# Digital__IO.net
KiCad netlist of a schematic drawn in Altium Designer
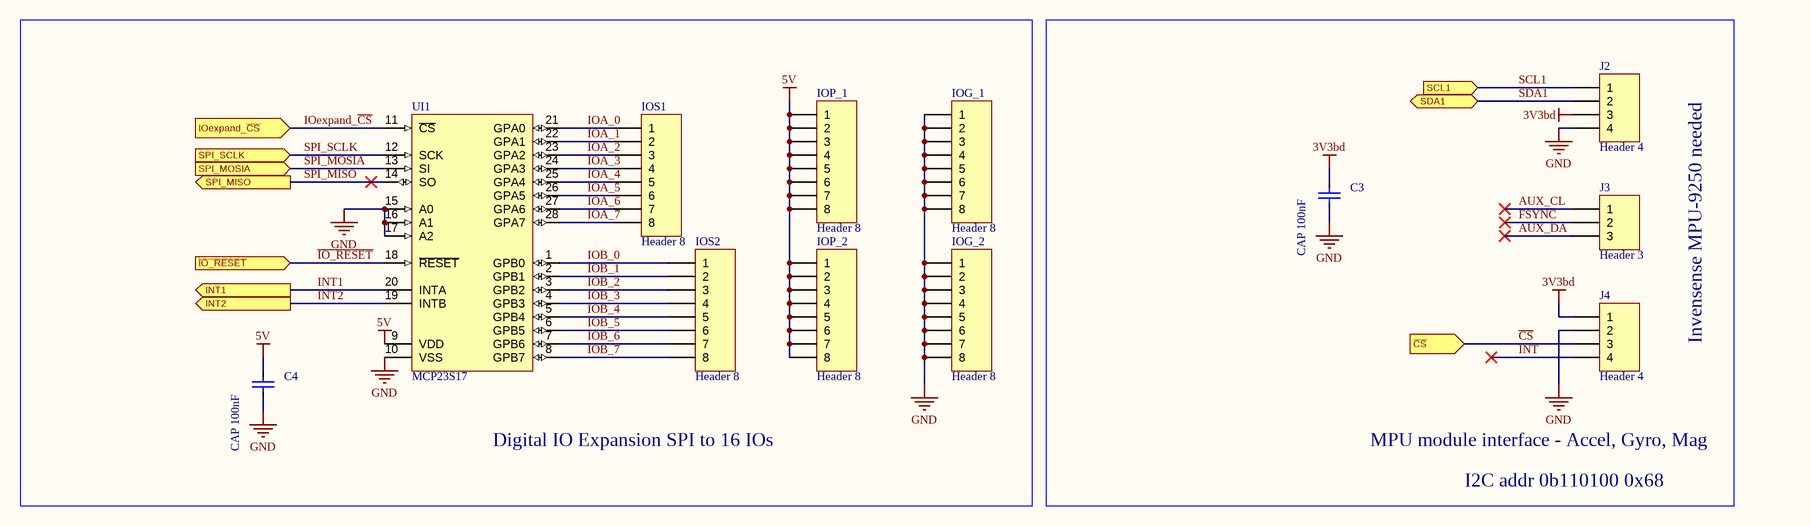
[diagram p0:  Digital_ IO.SchDoc]

(export (version "E")
  (design (tool "Eeschema 10.0.6"))
  (components
    (comp (ref "C3")
      (value "CAP 100nF")
      (footprint "0603C_L")
      (fields
        (field (name "MANUFACTURER") "Yageo")
        (field (name "MANUFACTURER PART NUMBER") "CC0603ZRY5V9BB104")
      )
      (libsource (lib "MHH -  Altium Advanced Course A365 01") (part "CMP-00119-2"))
    )
    (comp (ref "C4")
      (value "CAP 100nF")
      (footprint "0603C_L")
      (fields
        (field (name "MANUFACTURER") "Yageo")
        (field (name "MANUFACTURER PART NUMBER") "CC0603ZRY5V9BB104")
      )
      (libsource (lib "MHH -  Altium Advanced Course A365 01") (part "CMP-00119-2"))
    )
    (comp (ref "IOG_1")
      (value "Header 8")
      (footprint "HDR1X8")
      (description "Header, 8-Pin")
      (fields (field (name "PUBLISHER") "Altium Limited") (field (name "SOURCE") "WCT.SchLib"))
      (libsource (lib "MHH -  Altium Advanced Course A365 01") (part "Header 8"))
    )
    (comp (ref "IOG_2")
      (value "Header 8")
      (footprint "HDR1X8")
      (description "Header, 8-Pin")
      (fields (field (name "PUBLISHER") "Altium Limited") (field (name "SOURCE") "WCT.SchLib"))
      (libsource (lib "MHH -  Altium Advanced Course A365 01") (part "Header 8"))
    )
    (comp (ref "IOP_1")
      (value "Header 8")
      (footprint "HDR1X8")
      (description "Header, 8-Pin")
      (fields (field (name "PUBLISHER") "Altium Limited") (field (name "SOURCE") "WCT.SchLib"))
      (libsource (lib "MHH -  Altium Advanced Course A365 01") (part "Header 8"))
    )
    (comp (ref "IOP_2")
      (value "Header 8")
      (footprint "HDR1X8")
      (description "Header, 8-Pin")
      (fields (field (name "PUBLISHER") "Altium Limited") (field (name "SOURCE") "WCT.SchLib"))
      (libsource (lib "MHH -  Altium Advanced Course A365 01") (part "Header 8"))
    )
    (comp (ref "IOS1")
      (value "Header 8")
      (footprint "HDR1X8")
      (description "Header, 8-Pin")
      (fields (field (name "PUBLISHER") "Altium Limited") (field (name "SOURCE") "WCT.SchLib"))
      (libsource (lib "MHH -  Altium Advanced Course A365 01") (part "Header 8"))
    )
    (comp (ref "IOS2")
      (value "Header 8")
      (footprint "HDR1X8")
      (description "Header, 8-Pin")
      (fields (field (name "PUBLISHER") "Altium Limited") (field (name "SOURCE") "WCT.SchLib"))
      (libsource (lib "MHH -  Altium Advanced Course A365 01") (part "Header 8"))
    )
    (comp (ref "J2")
      (value "Header 4")
      (footprint "HDR1X4")
      (description "Header, 4-Pin")
      (fields (field (name "PUBLISHER") "Altium Limited") (field (name "SOURCE") "WCT.SchLib"))
      (libsource (lib "MHH -  Altium Advanced Course A365 01") (part "Header 4"))
    )
    (comp (ref "J3")
      (value "Header 3")
      (footprint "HDR1X3")
      (description "Header, 3-Pin")
      (fields (field (name "PUBLISHER") "Altium Limited") (field (name "SOURCE") "WCT.SchLib"))
      (libsource (lib "MHH -  Altium Advanced Course A365 01") (part "Header 3"))
    )
    (comp (ref "J4")
      (value "Header 4")
      (footprint "HDR1X4")
      (description "Header, 4-Pin")
      (fields (field (name "PUBLISHER") "Altium Limited") (field (name "SOURCE") "WCT.SchLib"))
      (libsource (lib "MHH -  Altium Advanced Course A365 01") (part "Header 4"))
    )
    (comp (ref "UI1")
      (value "MCP23S17")
      (footprint "SOIC-SO28_L")
      (description "16-Bit I/O Expander with Serial Interface, 28-Pin SOIC, Extended Temperature, Tape and Reel")
      (fields
        (field (name "MANUFACTURER") "Microchip")
        (field (name "MANUFACTURER PART NUMBER") "MCP23S17T-E/SO")
        (field (name "AVAILABLE PREVIEW IMAGES") "2D")
        (field (name "SOURCE") "WCT.SchLib")
      )
      (libsource (lib "MHH -  Altium Advanced Course A365 01") (part "MCP23S17"))
    )
  )
  (nets
    (net (code "1") (name "/AUX_CL") (class "Default")
      (node (ref "J3") (pin "1") (pinfunction "1_1") (pintype "passive+no_connect"))
    )
    (net (code "2") (name "/AUX_DA") (class "Default")
      (node (ref "J3") (pin "3") (pinfunction "3_3") (pintype "passive+no_connect"))
    )
    (net (code "3") (name "/FSYNC") (class "Default")
      (node (ref "J3") (pin "2") (pinfunction "2_2") (pintype "passive+no_connect"))
    )
    (net (code "4") (name "/INT") (class "Default")
      (node (ref "J4") (pin "4") (pinfunction "4_4") (pintype "passive+no_connect"))
    )
    (net (code "5") (name "/INT1") (class "Default")
      (node (ref "UI1") (pin "20") (pinfunction "INTA_20") (pintype "open_collector"))
    )
    (net (code "6") (name "/INT2") (class "Default")
      (node (ref "UI1") (pin "19") (pinfunction "INTB_19") (pintype "open_collector"))
    )
    (net (code "7") (name "/IOA_0") (class "Default")
      (node (ref "IOS1") (pin "1") (pinfunction "1_1") (pintype "passive"))
      (node (ref "UI1") (pin "21") (pinfunction "GPA0_21") (pintype "bidirectional"))
    )
    (net (code "8") (name "/IOA_1") (class "Default")
      (node (ref "IOS1") (pin "2") (pinfunction "2_2") (pintype "passive"))
      (node (ref "UI1") (pin "22") (pinfunction "GPA1_22") (pintype "bidirectional"))
    )
    (net (code "9") (name "/IOA_2") (class "Default")
      (node (ref "IOS1") (pin "3") (pinfunction "3_3") (pintype "passive"))
      (node (ref "UI1") (pin "23") (pinfunction "GPA2_23") (pintype "bidirectional"))
    )
    (net (code "10") (name "/IOA_3") (class "Default")
      (node (ref "IOS1") (pin "4") (pinfunction "4_4") (pintype "passive"))
      (node (ref "UI1") (pin "24") (pinfunction "GPA3_24") (pintype "bidirectional"))
    )
    (net (code "11") (name "/IOA_4") (class "Default")
      (node (ref "IOS1") (pin "5") (pinfunction "5_5") (pintype "passive"))
      (node (ref "UI1") (pin "25") (pinfunction "GPA4_25") (pintype "bidirectional"))
    )
    (net (code "12") (name "/IOA_5") (class "Default")
      (node (ref "IOS1") (pin "6") (pinfunction "6_6") (pintype "passive"))
      (node (ref "UI1") (pin "26") (pinfunction "GPA5_26") (pintype "bidirectional"))
    )
    (net (code "13") (name "/IOA_6") (class "Default")
      (node (ref "IOS1") (pin "7") (pinfunction "7_7") (pintype "passive"))
      (node (ref "UI1") (pin "27") (pinfunction "GPA6_27") (pintype "bidirectional"))
    )
    (net (code "14") (name "/IOA_7") (class "Default")
      (node (ref "IOS1") (pin "8") (pinfunction "8_8") (pintype "passive"))
      (node (ref "UI1") (pin "28") (pinfunction "GPA7_28") (pintype "bidirectional"))
    )
    (net (code "15") (name "/IOB_0") (class "Default")
      (node (ref "IOS2") (pin "1") (pinfunction "1_1") (pintype "passive"))
      (node (ref "UI1") (pin "1") (pinfunction "GPB0_1") (pintype "bidirectional"))
    )
    (net (code "16") (name "/IOB_1") (class "Default")
      (node (ref "IOS2") (pin "2") (pinfunction "2_2") (pintype "passive"))
      (node (ref "UI1") (pin "2") (pinfunction "GPB1_2") (pintype "bidirectional"))
    )
    (net (code "17") (name "/IOB_2") (class "Default")
      (node (ref "IOS2") (pin "3") (pinfunction "3_3") (pintype "passive"))
      (node (ref "UI1") (pin "3") (pinfunction "GPB2_3") (pintype "bidirectional"))
    )
    (net (code "18") (name "/IOB_3") (class "Default")
      (node (ref "IOS2") (pin "4") (pinfunction "4_4") (pintype "passive"))
      (node (ref "UI1") (pin "4") (pinfunction "GPB3_4") (pintype "bidirectional"))
    )
    (net (code "19") (name "/IOB_4") (class "Default")
      (node (ref "IOS2") (pin "5") (pinfunction "5_5") (pintype "passive"))
      (node (ref "UI1") (pin "5") (pinfunction "GPB4_5") (pintype "bidirectional"))
    )
    (net (code "20") (name "/IOB_5") (class "Default")
      (node (ref "IOS2") (pin "6") (pinfunction "6_6") (pintype "passive"))
      (node (ref "UI1") (pin "6") (pinfunction "GPB5_6") (pintype "bidirectional"))
    )
    (net (code "21") (name "/IOB_6") (class "Default")
      (node (ref "IOS2") (pin "7") (pinfunction "7_7") (pintype "passive"))
      (node (ref "UI1") (pin "7") (pinfunction "GPB6_7") (pintype "bidirectional"))
    )
    (net (code "22") (name "/IOB_7") (class "Default")
      (node (ref "IOS2") (pin "8") (pinfunction "8_8") (pintype "passive"))
      (node (ref "UI1") (pin "8") (pinfunction "GPB7_8") (pintype "bidirectional"))
    )
    (net (code "23") (name "/IO_RESET") (class "Default")
      (node (ref "UI1") (pin "18") (pinfunction "~{RESET}_18") (pintype "input"))
    )
    (net (code "24") (name "/IOexpand_~{CS}") (class "Default")
      (node (ref "UI1") (pin "11") (pinfunction "~{CS}_11") (pintype "input"))
    )
    (net (code "25") (name "/SCL1") (class "Default")
      (node (ref "J2") (pin "1") (pinfunction "1_1") (pintype "passive"))
    )
    (net (code "26") (name "/SDA1") (class "Default")
      (node (ref "J2") (pin "2") (pinfunction "2_2") (pintype "passive"))
    )
    (net (code "27") (name "/SPI_MISO") (class "Default")
      (node (ref "UI1") (pin "14") (pinfunction "SO_14") (pintype "bidirectional"))
    )
    (net (code "28") (name "/SPI_MOSIA") (class "Default")
      (node (ref "UI1") (pin "13") (pinfunction "SI_13") (pintype "input"))
    )
    (net (code "29") (name "/SPI_SCLK") (class "Default")
      (node (ref "UI1") (pin "12") (pinfunction "SCK_12") (pintype "input"))
    )
    (net (code "30") (name "/~{CS}") (class "Default")
      (node (ref "J4") (pin "3") (pinfunction "3_3") (pintype "passive"))
    )
    (net (code "31") (name "3V3bd") (class "Default")
      (node (ref "C3") (pin "2") (pinfunction "2_2") (pintype "passive"))
      (node (ref "J2") (pin "3") (pinfunction "3_3") (pintype "passive"))
      (node (ref "J4") (pin "1") (pinfunction "1_1") (pintype "passive"))
    )
    (net (code "32") (name "5V") (class "Default")
      (node (ref "C4") (pin "2") (pinfunction "2_2") (pintype "passive"))
      (node (ref "IOP_1") (pin "1") (pinfunction "1_1") (pintype "passive"))
      (node (ref "IOP_1") (pin "2") (pinfunction "2_2") (pintype "passive"))
      (node (ref "IOP_1") (pin "3") (pinfunction "3_3") (pintype "passive"))
      (node (ref "IOP_1") (pin "4") (pinfunction "4_4") (pintype "passive"))
      (node (ref "IOP_1") (pin "5") (pinfunction "5_5") (pintype "passive"))
      (node (ref "IOP_1") (pin "6") (pinfunction "6_6") (pintype "passive"))
      (node (ref "IOP_1") (pin "7") (pinfunction "7_7") (pintype "passive"))
      (node (ref "IOP_1") (pin "8") (pinfunction "8_8") (pintype "passive"))
      (node (ref "IOP_2") (pin "1") (pinfunction "1_1") (pintype "passive"))
      (node (ref "IOP_2") (pin "2") (pinfunction "2_2") (pintype "passive"))
      (node (ref "IOP_2") (pin "3") (pinfunction "3_3") (pintype "passive"))
      (node (ref "IOP_2") (pin "4") (pinfunction "4_4") (pintype "passive"))
      (node (ref "IOP_2") (pin "5") (pinfunction "5_5") (pintype "passive"))
      (node (ref "IOP_2") (pin "6") (pinfunction "6_6") (pintype "passive"))
      (node (ref "IOP_2") (pin "7") (pinfunction "7_7") (pintype "passive"))
      (node (ref "IOP_2") (pin "8") (pinfunction "8_8") (pintype "passive"))
      (node (ref "UI1") (pin "9") (pinfunction "VDD_9") (pintype "power_in"))
    )
    (net (code "33") (name "GND") (class "Default")
      (node (ref "C3") (pin "1") (pinfunction "1_1") (pintype "passive"))
      (node (ref "C4") (pin "1") (pinfunction "1_1") (pintype "passive"))
      (node (ref "IOG_1") (pin "1") (pinfunction "1_1") (pintype "passive"))
      (node (ref "IOG_1") (pin "2") (pinfunction "2_2") (pintype "passive"))
      (node (ref "IOG_1") (pin "3") (pinfunction "3_3") (pintype "passive"))
      (node (ref "IOG_1") (pin "4") (pinfunction "4_4") (pintype "passive"))
      (node (ref "IOG_1") (pin "5") (pinfunction "5_5") (pintype "passive"))
      (node (ref "IOG_1") (pin "6") (pinfunction "6_6") (pintype "passive"))
      (node (ref "IOG_1") (pin "7") (pinfunction "7_7") (pintype "passive"))
      (node (ref "IOG_1") (pin "8") (pinfunction "8_8") (pintype "passive"))
      (node (ref "IOG_2") (pin "1") (pinfunction "1_1") (pintype "passive"))
      (node (ref "IOG_2") (pin "2") (pinfunction "2_2") (pintype "passive"))
      (node (ref "IOG_2") (pin "3") (pinfunction "3_3") (pintype "passive"))
      (node (ref "IOG_2") (pin "4") (pinfunction "4_4") (pintype "passive"))
      (node (ref "IOG_2") (pin "5") (pinfunction "5_5") (pintype "passive"))
      (node (ref "IOG_2") (pin "6") (pinfunction "6_6") (pintype "passive"))
      (node (ref "IOG_2") (pin "7") (pinfunction "7_7") (pintype "passive"))
      (node (ref "IOG_2") (pin "8") (pinfunction "8_8") (pintype "passive"))
      (node (ref "J2") (pin "4") (pinfunction "4_4") (pintype "passive"))
      (node (ref "J4") (pin "2") (pinfunction "2_2") (pintype "passive"))
      (node (ref "UI1") (pin "10") (pinfunction "VSS_10") (pintype "power_in"))
      (node (ref "UI1") (pin "15") (pinfunction "A0_15") (pintype "input"))
      (node (ref "UI1") (pin "16") (pinfunction "A1_16") (pintype "input"))
      (node (ref "UI1") (pin "17") (pinfunction "A2_17") (pintype "input"))
    )
  )
)
